# attiny85_bo.net
KiCad netlist of a schematic drawn in EAGLE
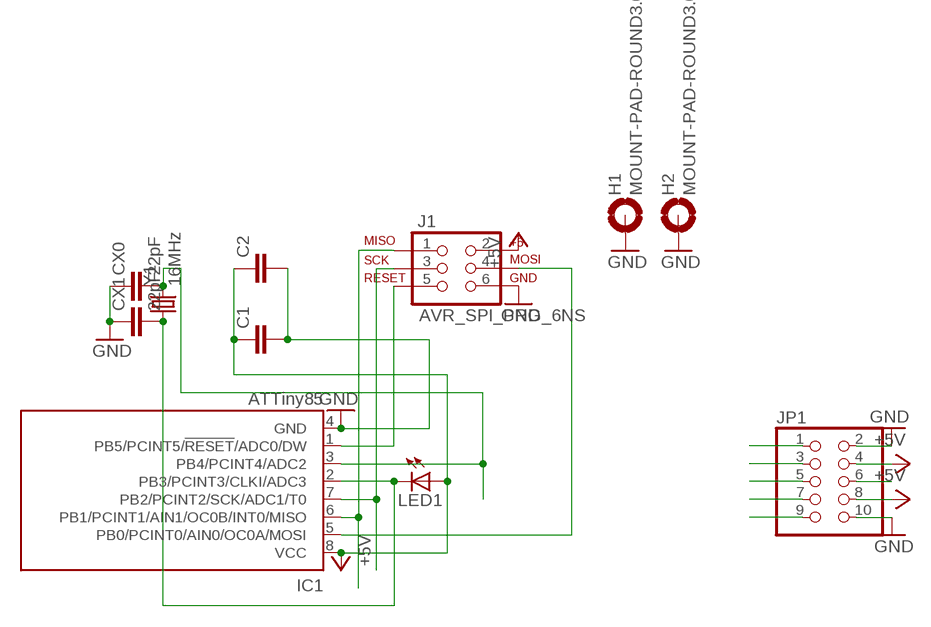
[diagram p0: schematic, sheet 1]

(export (version "E")
  (design (tool "Eeschema 10.0.6"))
  (components
    (comp (ref "C1")
      (value "C-EUC0805")
      (footprint "eagle-import:C0805")
      (libsource (lib "eagle-import") (part "C-EUC0805"))
    )
    (comp (ref "C2")
      (value "C-EUC0805")
      (footprint "eagle-import:C0805")
      (libsource (lib "eagle-import") (part "C-EUC0805"))
    )
    (comp (ref "CX0")
      (value "22pF")
      (footprint "eagle-import:C0603")
      (libsource (lib "eagle-import") (part "C-EUC0603"))
    )
    (comp (ref "CX1")
      (value "22pF")
      (footprint "eagle-import:C0603")
      (libsource (lib "eagle-import") (part "C-EUC0603"))
    )
    (comp (ref "H1")
      (value "MOUNT-PAD-ROUND3.0")
      (footprint "eagle-import:3,0-PAD")
      (libsource (lib "eagle-import") (part "MOUNT-PAD-ROUND3.0"))
    )
    (comp (ref "H2")
      (value "MOUNT-PAD-ROUND3.0")
      (footprint "eagle-import:3,0-PAD")
      (libsource (lib "eagle-import") (part "MOUNT-PAD-ROUND3.0"))
    )
    (comp (ref "IC1")
      (value "ATTiny85")
      (footprint "eagle-import:8S2")
      (fields (field (name "MPN") "ATTINY13-20SU"))
      (libsource (lib "eagle-import") (part "TINY13SU-20"))
    )
    (comp (ref "J1")
      (value "AVR_SPI_PRG_6NS")
      (footprint "eagle-import:2X3-NS")
      (libsource (lib "eagle-import") (part "AVR_SPI_PRG_6NS"))
    )
    (comp (ref "JP1")
      (value "PINHD-2X5")
      (footprint "eagle-import:2X05")
      (libsource (lib "eagle-import") (part "PINHD-2X5"))
    )
    (comp (ref "LED1")
      (value "LED0603")
      (footprint "eagle-import:LED-0603")
      (libsource (lib "eagle-import") (part "LED0603"))
    )
    (comp (ref "Y1")
      (value "16MHz")
      (footprint "eagle-import:CRYSTAL-SMD-5X3")
      (libsource (lib "eagle-import") (part "CRYSTAL5X3"))
    )
  )
  (nets
    (net (code "1") (name "+5V") (class "Default")
      (node (ref "C1") (pin "1") (pinfunction "1_1") (pintype "passive"))
      (node (ref "C2") (pin "1") (pinfunction "1_1") (pintype "passive"))
      (node (ref "IC1") (pin "8") (pinfunction "VCC_8") (pintype "power_in"))
      (node (ref "J1") (pin "2") (pinfunction "2_2") (pintype "passive"))
      (node (ref "JP1") (pin "4") (pinfunction "4_4") (pintype "passive"))
      (node (ref "JP1") (pin "8") (pinfunction "8_8") (pintype "passive"))
      (node (ref "LED1") (pin "A") (pinfunction "A_A") (pintype "passive"))
    )
    (net (code "2") (name "/PB0") (class "Default")
      (node (ref "IC1") (pin "5") (pinfunction "PB0/PCINT0/AIN0/OC0A/MOSI_5") (pintype "bidirectional"))
      (node (ref "J1") (pin "4") (pinfunction "4_4") (pintype "passive"))
      (node (ref "JP1") (pin "1") (pinfunction "1_1") (pintype "passive"))
    )
    (net (code "3") (name "/PB1") (class "Default")
      (node (ref "IC1") (pin "6") (pinfunction "PB1/PCINT1/AIN1/OC0B/INT0/MISO_6") (pintype "bidirectional"))
      (node (ref "J1") (pin "1") (pinfunction "1_1") (pintype "passive"))
      (node (ref "JP1") (pin "3") (pinfunction "3_3") (pintype "passive"))
    )
    (net (code "4") (name "/PB2") (class "Default")
      (node (ref "IC1") (pin "7") (pinfunction "PB2/PCINT2/SCK/ADC1/T0_7") (pintype "bidirectional"))
      (node (ref "J1") (pin "3") (pinfunction "3_3") (pintype "passive"))
      (node (ref "JP1") (pin "5") (pinfunction "5_5") (pintype "passive"))
    )
    (net (code "5") (name "/PB3") (class "Default")
      (node (ref "CX1") (pin "2") (pinfunction "2_2") (pintype "passive"))
      (node (ref "IC1") (pin "2") (pinfunction "PB3/PCINT3/CLKI/ADC3_2") (pintype "bidirectional"))
      (node (ref "JP1") (pin "7") (pinfunction "7_7") (pintype "passive"))
      (node (ref "LED1") (pin "C") (pinfunction "C_C") (pintype "passive"))
      (node (ref "Y1") (pin "1") (pinfunction "1_1") (pintype "passive"))
    )
    (net (code "6") (name "/PB4") (class "Default")
      (node (ref "CX0") (pin "2") (pinfunction "2_2") (pintype "passive"))
      (node (ref "IC1") (pin "3") (pinfunction "PB4/PCINT4/ADC2_3") (pintype "bidirectional"))
      (node (ref "JP1") (pin "9") (pinfunction "9_9") (pintype "passive"))
      (node (ref "Y1") (pin "3") (pinfunction "2_3") (pintype "passive"))
    )
    (net (code "7") (name "/PB5") (class "Default")
      (node (ref "IC1") (pin "1") (pinfunction "PB5/PCINT5/~{RESET}/ADC0/DW_1") (pintype "bidirectional"))
      (node (ref "J1") (pin "5") (pinfunction "5_5") (pintype "passive"))
      (node (ref "JP1") (pin "6") (pinfunction "6_6") (pintype "passive"))
    )
    (net (code "8") (name "GND") (class "Default")
      (node (ref "C1") (pin "2") (pinfunction "2_2") (pintype "passive"))
      (node (ref "C2") (pin "2") (pinfunction "2_2") (pintype "passive"))
      (node (ref "CX0") (pin "1") (pinfunction "1_1") (pintype "passive"))
      (node (ref "CX1") (pin "1") (pinfunction "1_1") (pintype "passive"))
      (node (ref "H1") (pin "B3,0") (pinfunction "MOUNT_B3,0") (pintype "passive"))
      (node (ref "H2") (pin "B3,0") (pinfunction "MOUNT_B3,0") (pintype "passive"))
      (node (ref "IC1") (pin "4") (pinfunction "GND_4") (pintype "power_in"))
      (node (ref "J1") (pin "6") (pinfunction "6_6") (pintype "passive"))
      (node (ref "JP1") (pin "10") (pinfunction "10_10") (pintype "passive"))
      (node (ref "JP1") (pin "2") (pinfunction "2_2") (pintype "passive"))
    )
  )
)
